# Stage2Sensors.net
KiCad netlist of a schematic drawn in Altium Designer
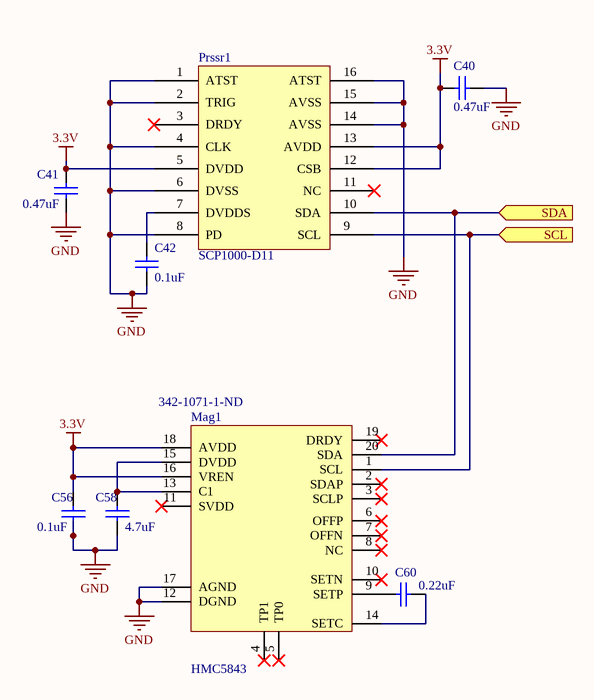
[diagram p0: Stage2Sensors.SchDoc]

(export (version "E")
  (design (tool "Eeschema 10.0.6"))
  (components
    (comp (ref "C40")
      (value "0.47uF")
      (footprint "0603_CAP")
      (description "Capacitor")
      (fields (field (name "Comment") "X7R Cap") (field (name "PUBLISHER") "Altium Limited"))
      (libsource (lib "Miscellaneous Devices") (part "Cap"))
    )
    (comp (ref "C41")
      (value "0.47uF")
      (footprint "0603_CAP")
      (description "Capacitor")
      (fields (field (name "Comment") "X7R Cap") (field (name "PUBLISHER") "Altium Limited"))
      (libsource (lib "Miscellaneous Devices") (part "Cap"))
    )
    (comp (ref "C42")
      (value "0.1uF")
      (footprint "0603_CAP")
      (description "Capacitor")
      (fields (field (name "Comment") "X7R Cap") (field (name "PUBLISHER") "Altium Limited"))
      (libsource (lib "Miscellaneous Devices") (part "Cap"))
    )
    (comp (ref "C56")
      (value "0.1uF")
      (footprint "0603_CAP")
      (description "Capacitor")
      (fields (field (name "Comment") "X7R Cap") (field (name "PUBLISHER") "Altium Limited"))
      (libsource (lib "Miscellaneous Devices") (part "Cap"))
    )
    (comp (ref "C58")
      (value "4.7uF")
      (footprint "0603_CAP")
      (description "Capacitor")
      (fields (field (name "Comment") "X7R Cap") (field (name "PUBLISHER") "Altium Limited"))
      (libsource (lib "Miscellaneous Devices") (part "Cap"))
    )
    (comp (ref "C60")
      (value "0.22uF")
      (footprint "0603_CAP")
      (description "Capacitor")
      (fields (field (name "Comment") "X7R Cap") (field (name "PUBLISHER") "Altium Limited"))
      (libsource (lib "Miscellaneous Devices") (part "Cap"))
    )
    (comp (ref "Mag1")
      (value "HMC5843")
      (footprint "HMC5843")
      (description "SENSOR MAGNETIC 3 AXIS 20-LCC")
      (fields
        (field (name "SUPPLIER PART NUMBER 2") "342-1071-1-ND")
        (field (name "MANUFACTURER") "Honeywell Microelectronics & Precision Sensors")
        (field (name "MANUFACTURER PART NUMBER") "HMC5843-TR")
      )
      (libsource (lib "Components") (part "Magnetometer HMC5843"))
    )
    (comp (ref "Prssr1")
      (value "SCP1000-D11")
      (footprint "SCP1000-D11")
      (libsource (lib "Components") (part "SCP1000-D11"))
    )
  )
  (nets
    (net (code "1") (name "/SCL") (class "Default")
      (node (ref "Mag1") (pin "1") (pinfunction "SCL_1") (pintype "passive"))
      (node (ref "Prssr1") (pin "9") (pinfunction "SCL_9") (pintype "passive"))
    )
    (net (code "2") (name "/SDA") (class "Default")
      (node (ref "Mag1") (pin "20") (pinfunction "SDA_20") (pintype "passive"))
      (node (ref "Prssr1") (pin "10") (pinfunction "SDA_10") (pintype "passive"))
    )
    (net (code "3") (name "3.3V") (class "Default")
      (node (ref "C40") (pin "2") (pinfunction "2_2") (pintype "passive"))
      (node (ref "C41") (pin "2") (pinfunction "2_2") (pintype "passive"))
      (node (ref "C56") (pin "2") (pinfunction "2_2") (pintype "passive"))
      (node (ref "Mag1") (pin "16") (pinfunction "VREN_16") (pintype "passive"))
      (node (ref "Mag1") (pin "18") (pinfunction "AVDD_18") (pintype "passive"))
      (node (ref "Prssr1") (pin "12") (pinfunction "CSB_12") (pintype "passive"))
      (node (ref "Prssr1") (pin "13") (pinfunction "AVDD_13") (pintype "passive"))
      (node (ref "Prssr1") (pin "5") (pinfunction "DVDD_5") (pintype "passive"))
    )
    (net (code "4") (name "GND") (class "Default")
      (node (ref "C40") (pin "1") (pinfunction "1_1") (pintype "passive"))
      (node (ref "C41") (pin "1") (pinfunction "1_1") (pintype "passive"))
      (node (ref "C42") (pin "2") (pinfunction "2_2") (pintype "passive"))
      (node (ref "C56") (pin "1") (pinfunction "1_1") (pintype "passive"))
      (node (ref "C58") (pin "1") (pinfunction "1_1") (pintype "passive"))
      (node (ref "Mag1") (pin "12") (pinfunction "DGND_12") (pintype "passive"))
      (node (ref "Mag1") (pin "17") (pinfunction "AGND_17") (pintype "passive"))
      (node (ref "Prssr1") (pin "1") (pinfunction "ATST_1") (pintype "passive"))
      (node (ref "Prssr1") (pin "14") (pinfunction "AVSS_14") (pintype "passive"))
      (node (ref "Prssr1") (pin "15") (pinfunction "AVSS_15") (pintype "passive"))
      (node (ref "Prssr1") (pin "16") (pinfunction "ATST_16") (pintype "passive"))
      (node (ref "Prssr1") (pin "2") (pinfunction "TRIG_2") (pintype "passive"))
      (node (ref "Prssr1") (pin "4") (pinfunction "CLK_4") (pintype "passive"))
      (node (ref "Prssr1") (pin "6") (pinfunction "DVSS_6") (pintype "passive"))
      (node (ref "Prssr1") (pin "8") (pinfunction "PD_8") (pintype "passive"))
    )
    (net (code "5") (name "Net-(Mag1-C1)") (class "Default")
      (node (ref "C58") (pin "2") (pinfunction "2_2") (pintype "passive"))
      (node (ref "Mag1") (pin "13") (pinfunction "C1_13") (pintype "passive"))
      (node (ref "Mag1") (pin "15") (pinfunction "DVDD_15") (pintype "passive"))
    )
    (net (code "6") (name "Net-(Mag1-SETC)") (class "Default")
      (node (ref "C60") (pin "1") (pinfunction "1_1") (pintype "passive"))
      (node (ref "Mag1") (pin "14") (pinfunction "SETC_14") (pintype "passive"))
    )
    (net (code "7") (name "Net-(Mag1-SETP)") (class "Default")
      (node (ref "C60") (pin "2") (pinfunction "2_2") (pintype "passive"))
      (node (ref "Mag1") (pin "9") (pinfunction "SETP_9") (pintype "passive"))
    )
    (net (code "8") (name "Net-(Prssr1-DVDDS)") (class "Default")
      (node (ref "C42") (pin "1") (pinfunction "1_1") (pintype "passive"))
      (node (ref "Prssr1") (pin "7") (pinfunction "DVDDS_7") (pintype "passive"))
    )
    (net (code "9") (name "unconnected-(Mag1-DRDY-Pad19)") (class "Default")
      (node (ref "Mag1") (pin "19") (pinfunction "DRDY_19") (pintype "passive+no_connect"))
    )
    (net (code "10") (name "unconnected-(Mag1-NC-Pad8)") (class "Default")
      (node (ref "Mag1") (pin "8") (pinfunction "NC_8") (pintype "passive+no_connect"))
    )
    (net (code "11") (name "unconnected-(Mag1-OFFN-Pad7)") (class "Default")
      (node (ref "Mag1") (pin "7") (pinfunction "OFFN_7") (pintype "passive+no_connect"))
    )
    (net (code "12") (name "unconnected-(Mag1-OFFP-Pad6)") (class "Default")
      (node (ref "Mag1") (pin "6") (pinfunction "OFFP_6") (pintype "passive+no_connect"))
    )
    (net (code "13") (name "unconnected-(Mag1-SCLP-Pad3)") (class "Default")
      (node (ref "Mag1") (pin "3") (pinfunction "SCLP_3") (pintype "passive+no_connect"))
    )
    (net (code "14") (name "unconnected-(Mag1-SDAP-Pad2)") (class "Default")
      (node (ref "Mag1") (pin "2") (pinfunction "SDAP_2") (pintype "passive+no_connect"))
    )
    (net (code "15") (name "unconnected-(Mag1-SETN-Pad10)") (class "Default")
      (node (ref "Mag1") (pin "10") (pinfunction "SETN_10") (pintype "passive+no_connect"))
    )
    (net (code "16") (name "unconnected-(Mag1-SVDD-Pad11)") (class "Default")
      (node (ref "Mag1") (pin "11") (pinfunction "SVDD_11") (pintype "passive+no_connect"))
    )
    (net (code "17") (name "unconnected-(Mag1-TP0-Pad5)") (class "Default")
      (node (ref "Mag1") (pin "5") (pinfunction "TP0_5") (pintype "passive+no_connect"))
    )
    (net (code "18") (name "unconnected-(Mag1-TP1-Pad4)") (class "Default")
      (node (ref "Mag1") (pin "4") (pinfunction "TP1_4") (pintype "passive+no_connect"))
    )
    (net (code "19") (name "unconnected-(Prssr1-DRDY-Pad3)") (class "Default")
      (node (ref "Prssr1") (pin "3") (pinfunction "DRDY_3") (pintype "passive+no_connect"))
    )
    (net (code "20") (name "unconnected-(Prssr1-NC-Pad11)") (class "Default")
      (node (ref "Prssr1") (pin "11") (pinfunction "NC_11") (pintype "passive+no_connect"))
    )
  )
)
